# Main.net
KiCad netlist of a schematic drawn in EAGLE
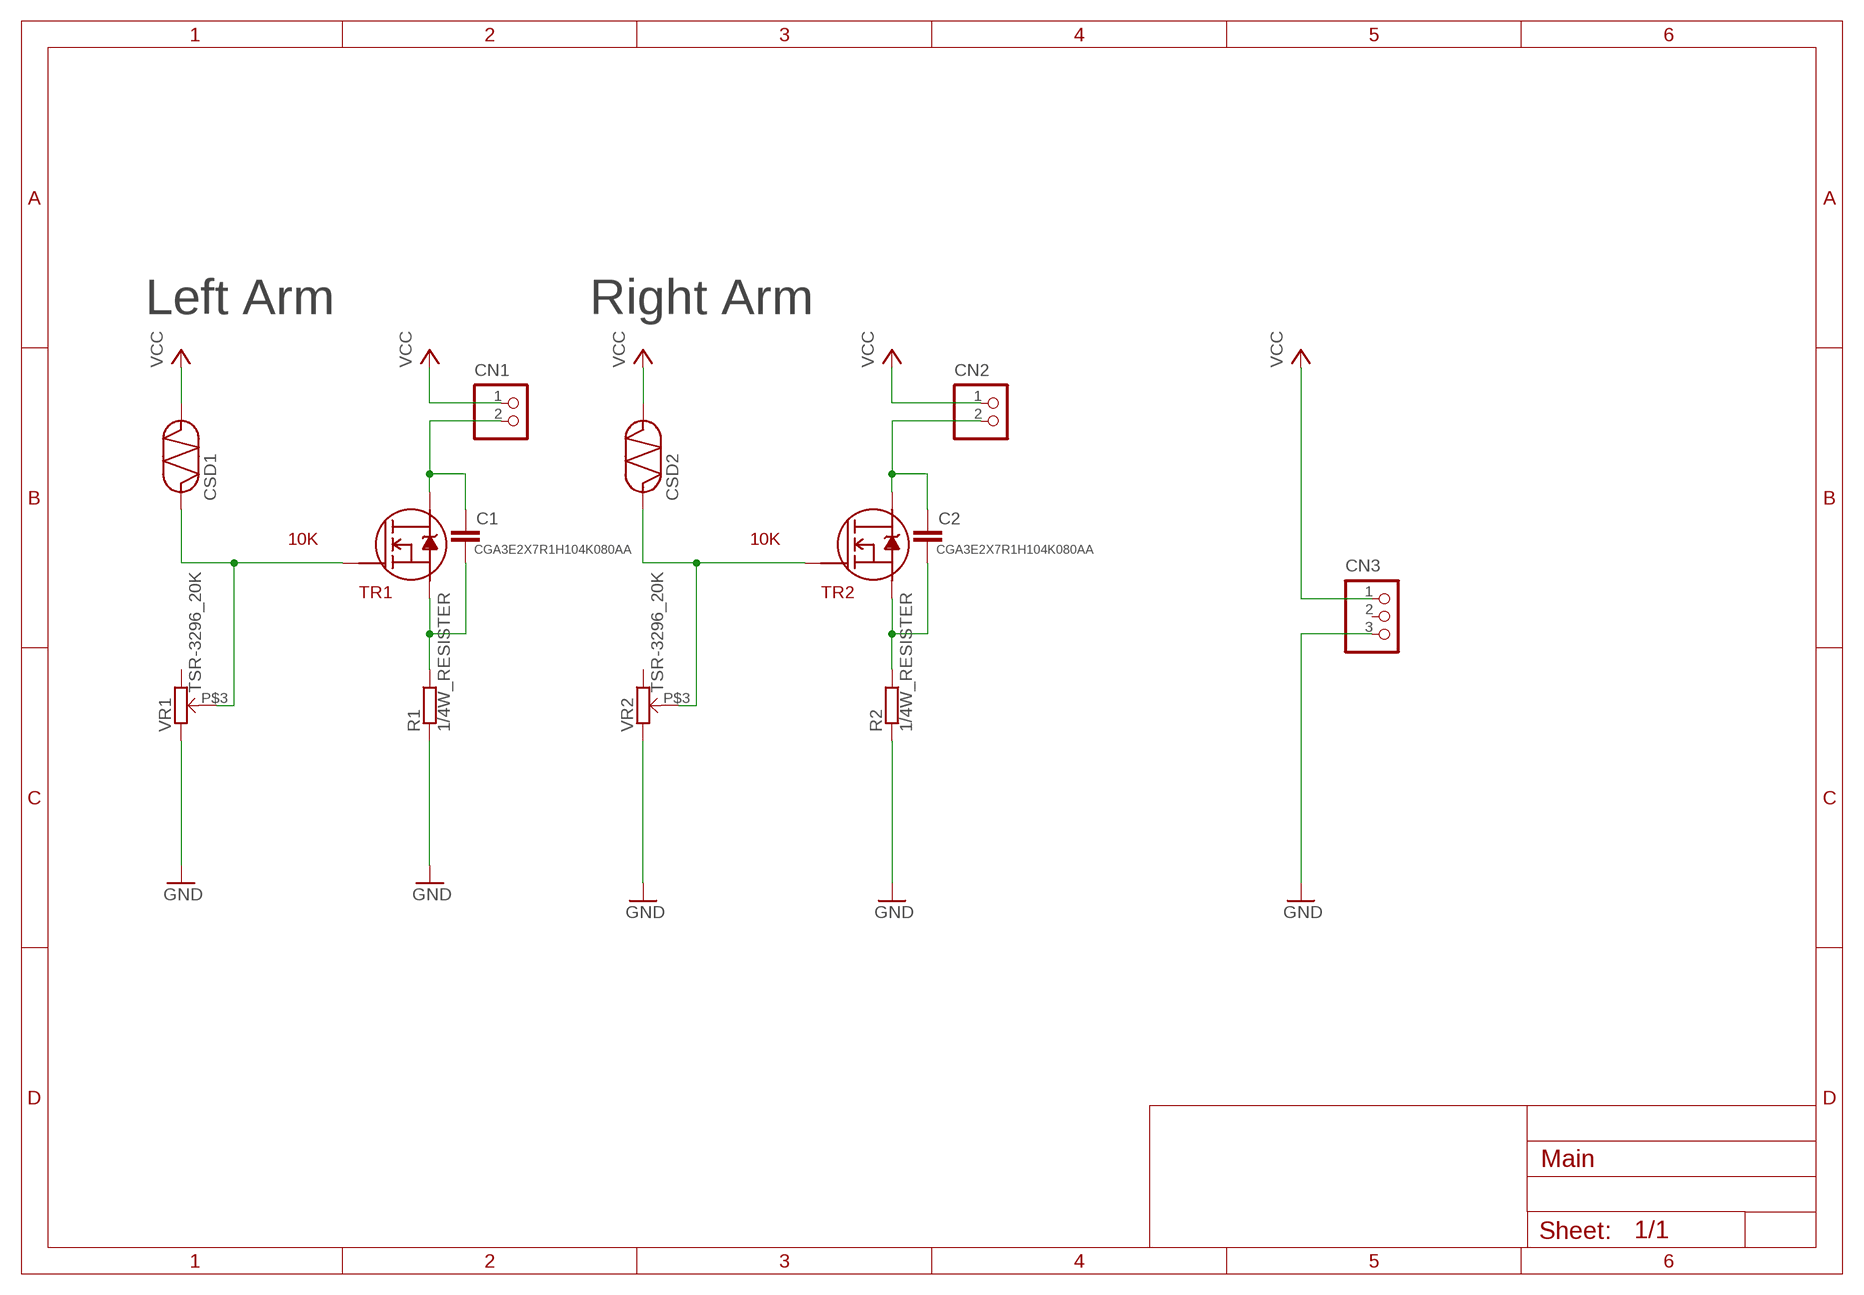
[diagram p0: schematic, sheet 1]

(export (version "E")
  (design (tool "Eeschema 10.0.6"))
  (components
    (comp (ref "C1")
      (value "CGA3E2X7R1H104K080AA")
      (footprint "eagle-import:0603")
      (libsource (lib "eagle-import") (part "CGA3E2X7R1H104K080AA"))
    )
    (comp (ref "C2")
      (value "CGA3E2X7R1H104K080AA")
      (footprint "eagle-import:0603")
      (libsource (lib "eagle-import") (part "CGA3E2X7R1H104K080AA"))
    )
    (comp (ref "CN1")
      (value "B2B-XH-A")
      (footprint "eagle-import:B2B-XH-A")
      (libsource (lib "eagle-import") (part "B2B-XH-A"))
    )
    (comp (ref "CN2")
      (value "B2B-XH-A")
      (footprint "eagle-import:B2B-XH-A")
      (libsource (lib "eagle-import") (part "B2B-XH-A"))
    )
    (comp (ref "CN3")
      (value "B3B-XH-A")
      (footprint "eagle-import:B3B-XH-A")
      (libsource (lib "eagle-import") (part "B3B-XH-A"))
    )
    (comp (ref "CSD1")
      (value "GL5528")
      (footprint "eagle-import:GL5528")
      (libsource (lib "eagle-import") (part "GL5528"))
    )
    (comp (ref "CSD2")
      (value "GL5528")
      (footprint "eagle-import:GL5528")
      (libsource (lib "eagle-import") (part "GL5528"))
    )
    (comp (ref "R1")
      (value "1/4W_RESISTER")
      (footprint "eagle-import:MF1_4")
      (libsource (lib "eagle-import") (part "1/4W_RESISTER"))
    )
    (comp (ref "R2")
      (value "1/4W_RESISTER")
      (footprint "eagle-import:MF1_4")
      (libsource (lib "eagle-import") (part "1/4W_RESISTER"))
    )
    (comp (ref "TR1")
      (value "RN5006")
      (footprint "eagle-import:SC-62")
      (libsource (lib "eagle-import") (part "RN5006"))
    )
    (comp (ref "TR2")
      (value "RN5006")
      (footprint "eagle-import:SC-62")
      (libsource (lib "eagle-import") (part "RN5006"))
    )
    (comp (ref "VR1")
      (value "TSR-3296_20K")
      (footprint "eagle-import:TSR-3296")
      (libsource (lib "eagle-import") (part "TSR-3296_20K"))
    )
    (comp (ref "VR2")
      (value "TSR-3296_20K")
      (footprint "eagle-import:TSR-3296")
      (libsource (lib "eagle-import") (part "TSR-3296_20K"))
    )
  )
  (nets
    (net (code "1") (name "GND") (class "Default")
      (node (ref "CN3") (pin "3") (pinfunction "3_3") (pintype "passive"))
      (node (ref "R1") (pin "P$2") (pinfunction "2_P$2") (pintype "passive"))
      (node (ref "R2") (pin "P$2") (pinfunction "2_P$2") (pintype "passive"))
      (node (ref "VR1") (pin "P$2") (pinfunction "2_P$2") (pintype "passive"))
      (node (ref "VR2") (pin "P$2") (pinfunction "2_P$2") (pintype "passive"))
    )
    (net (code "2") (name "Net-(C1-1)") (class "Default")
      (node (ref "C1") (pin "P$1") (pinfunction "1_P$1") (pintype "passive"))
      (node (ref "CN1") (pin "2") (pinfunction "2_2") (pintype "passive"))
      (node (ref "TR1") (pin "E") (pinfunction "D_E") (pintype "bidirectional"))
    )
    (net (code "3") (name "Net-(C1-2)") (class "Default")
      (node (ref "C1") (pin "P$2") (pinfunction "2_P$2") (pintype "passive"))
      (node (ref "R1") (pin "P$1") (pinfunction "1_P$1") (pintype "passive"))
      (node (ref "TR1") (pin "C1") (pinfunction "S_C1") (pintype "bidirectional"))
      (node (ref "TR1") (pin "C2") (pinfunction "S_C2") (pintype "bidirectional"))
    )
    (net (code "4") (name "Net-(C2-1)") (class "Default")
      (node (ref "C2") (pin "P$1") (pinfunction "1_P$1") (pintype "passive"))
      (node (ref "CN2") (pin "2") (pinfunction "2_2") (pintype "passive"))
      (node (ref "TR2") (pin "E") (pinfunction "D_E") (pintype "bidirectional"))
    )
    (net (code "5") (name "Net-(C2-2)") (class "Default")
      (node (ref "C2") (pin "P$2") (pinfunction "2_P$2") (pintype "passive"))
      (node (ref "R2") (pin "P$1") (pinfunction "1_P$1") (pintype "passive"))
      (node (ref "TR2") (pin "C1") (pinfunction "S_C1") (pintype "bidirectional"))
      (node (ref "TR2") (pin "C2") (pinfunction "S_C2") (pintype "bidirectional"))
    )
    (net (code "6") (name "Net-(TR1-G)") (class "Default")
      (node (ref "CSD1") (pin "P$1") (pinfunction "P$1_P$1") (pintype "bidirectional"))
      (node (ref "TR1") (pin "B") (pinfunction "G_B") (pintype "bidirectional"))
      (node (ref "VR1") (pin "P$3") (pinfunction "P$1_P$3") (pintype "bidirectional"))
    )
    (net (code "7") (name "Net-(TR2-G)") (class "Default")
      (node (ref "CSD2") (pin "P$1") (pinfunction "P$1_P$1") (pintype "bidirectional"))
      (node (ref "TR2") (pin "B") (pinfunction "G_B") (pintype "bidirectional"))
      (node (ref "VR2") (pin "P$3") (pinfunction "P$1_P$3") (pintype "bidirectional"))
    )
    (net (code "8") (name "VCC") (class "Default")
      (node (ref "CN1") (pin "1") (pinfunction "1_1") (pintype "passive"))
      (node (ref "CN2") (pin "1") (pinfunction "1_1") (pintype "passive"))
      (node (ref "CN3") (pin "1") (pinfunction "1_1") (pintype "passive"))
      (node (ref "CSD1") (pin "P$2") (pinfunction "P$2_P$2") (pintype "bidirectional"))
      (node (ref "CSD2") (pin "P$2") (pinfunction "P$2_P$2") (pintype "bidirectional"))
    )
    (net (code "9") (name "unconnected-(CN3-Pad2)") (class "Default")
      (node (ref "CN3") (pin "2") (pinfunction "2_2") (pintype "passive"))
    )
    (net (code "10") (name "unconnected-(VR1-1-PadP$1)") (class "Default")
      (node (ref "VR1") (pin "P$1") (pinfunction "1_P$1") (pintype "passive"))
    )
    (net (code "11") (name "unconnected-(VR2-1-PadP$1)") (class "Default")
      (node (ref "VR2") (pin "P$1") (pinfunction "1_P$1") (pintype "passive"))
    )
  )
)
